# Video.net
KiCad netlist of a schematic drawn in Altium Designer
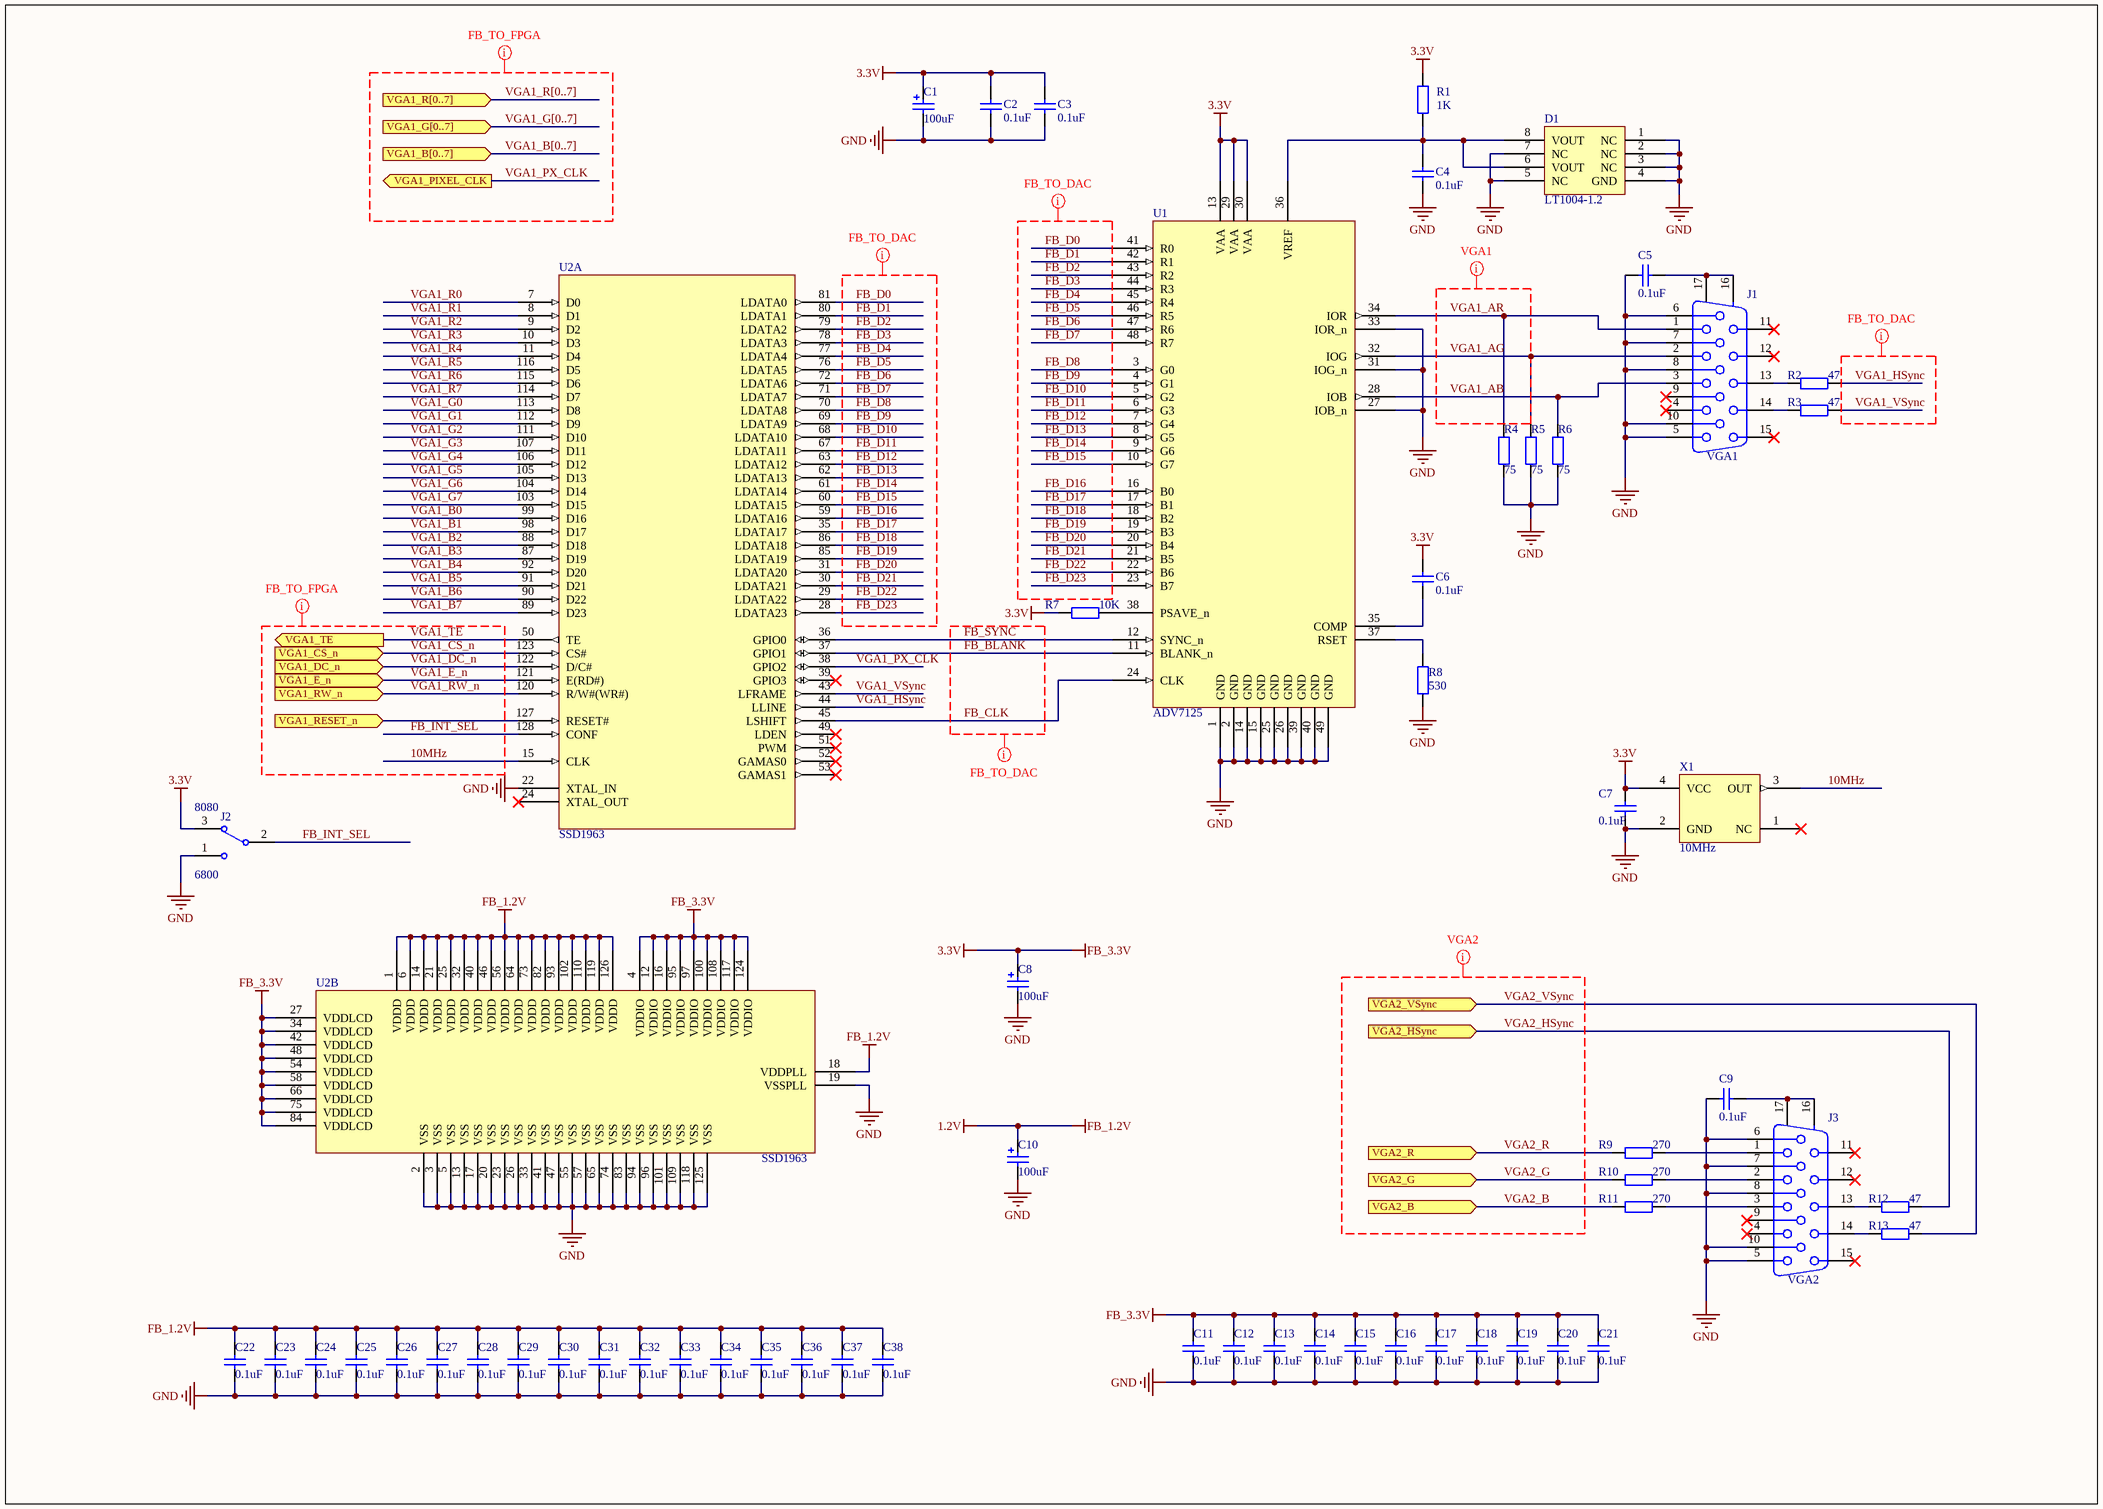
[diagram p0: Video.SchDoc]

(export (version "E")
  (design (tool "Eeschema 10.0.6"))
  (components
    (comp (ref "C1")
      (value "100uF")
      (footprint "C1206_POLARIZED")
      (description "Polarized Capacitor (Axial)")
      (fields (field (name "Comment") "Cap Pol2") (field (name "PUBLISHER") "Altium Limited"))
      (libsource (lib "Miscellaneous Devices") (part "Cap Pol2"))
    )
    (comp (ref "C2")
      (value "0.1uF")
      (footprint "0402")
      (description "Capacitor")
      (fields (field (name "Comment") "Cap") (field (name "PUBLISHER") "Altium Limited"))
      (libsource (lib "Miscellaneous Devices") (part "Cap"))
    )
    (comp (ref "C3")
      (value "0.1uF")
      (footprint "0402")
      (description "Capacitor")
      (fields (field (name "Comment") "Cap") (field (name "PUBLISHER") "Altium Limited"))
      (libsource (lib "Miscellaneous Devices") (part "Cap"))
    )
    (comp (ref "C4")
      (value "0.1uF")
      (footprint "0402")
      (description "Capacitor")
      (fields (field (name "Comment") "Cap") (field (name "PUBLISHER") "Altium Limited"))
      (libsource (lib "Miscellaneous Devices") (part "Cap"))
    )
    (comp (ref "C5")
      (value "0.1uF")
      (footprint "0402")
      (description "Capacitor")
      (fields (field (name "Comment") "Cap") (field (name "PUBLISHER") "Altium Limited"))
      (libsource (lib "Miscellaneous Devices") (part "Cap"))
    )
    (comp (ref "C6")
      (value "0.1uF")
      (footprint "0402")
      (description "Capacitor")
      (fields (field (name "Comment") "Cap") (field (name "PUBLISHER") "Altium Limited"))
      (libsource (lib "Miscellaneous Devices") (part "Cap"))
    )
    (comp (ref "C7")
      (value "0.1uF")
      (footprint "0402")
      (description "Capacitor")
      (fields (field (name "Comment") "Cap") (field (name "PUBLISHER") "Altium Limited"))
      (libsource (lib "Miscellaneous Devices") (part "Cap"))
    )
    (comp (ref "C8")
      (value "100uF")
      (footprint "C1206_POLARIZED")
      (description "Polarized Capacitor (Axial)")
      (fields (field (name "Comment") "Cap Pol2") (field (name "PUBLISHER") "Altium Limited"))
      (libsource (lib "Miscellaneous Devices") (part "Cap Pol2"))
    )
    (comp (ref "C9")
      (value "0.1uF")
      (footprint "0402")
      (description "Capacitor")
      (fields (field (name "Comment") "Cap") (field (name "PUBLISHER") "Altium Limited"))
      (libsource (lib "Miscellaneous Devices") (part "Cap"))
    )
    (comp (ref "C10")
      (value "100uF")
      (footprint "C1206_POLARIZED")
      (description "Polarized Capacitor (Axial)")
      (fields (field (name "Comment") "Cap Pol2") (field (name "PUBLISHER") "Altium Limited"))
      (libsource (lib "Miscellaneous Devices") (part "Cap Pol2"))
    )
    (comp (ref "C11")
      (value "0.1uF")
      (footprint "0402")
      (description "Capacitor")
      (fields (field (name "Comment") "Cap") (field (name "PUBLISHER") "Altium Limited"))
      (libsource (lib "Miscellaneous Devices") (part "Cap"))
    )
    (comp (ref "C12")
      (value "0.1uF")
      (footprint "0402")
      (description "Capacitor")
      (fields (field (name "Comment") "Cap") (field (name "PUBLISHER") "Altium Limited"))
      (libsource (lib "Miscellaneous Devices") (part "Cap"))
    )
    (comp (ref "C13")
      (value "0.1uF")
      (footprint "0402")
      (description "Capacitor")
      (fields (field (name "Comment") "Cap") (field (name "PUBLISHER") "Altium Limited"))
      (libsource (lib "Miscellaneous Devices") (part "Cap"))
    )
    (comp (ref "C14")
      (value "0.1uF")
      (footprint "0402")
      (description "Capacitor")
      (fields (field (name "Comment") "Cap") (field (name "PUBLISHER") "Altium Limited"))
      (libsource (lib "Miscellaneous Devices") (part "Cap"))
    )
    (comp (ref "C15")
      (value "0.1uF")
      (footprint "0402")
      (description "Capacitor")
      (fields (field (name "Comment") "Cap") (field (name "PUBLISHER") "Altium Limited"))
      (libsource (lib "Miscellaneous Devices") (part "Cap"))
    )
    (comp (ref "C16")
      (value "0.1uF")
      (footprint "0402")
      (description "Capacitor")
      (fields (field (name "Comment") "Cap") (field (name "PUBLISHER") "Altium Limited"))
      (libsource (lib "Miscellaneous Devices") (part "Cap"))
    )
    (comp (ref "C17")
      (value "0.1uF")
      (footprint "0402")
      (description "Capacitor")
      (fields (field (name "Comment") "Cap") (field (name "PUBLISHER") "Altium Limited"))
      (libsource (lib "Miscellaneous Devices") (part "Cap"))
    )
    (comp (ref "C18")
      (value "0.1uF")
      (footprint "0402")
      (description "Capacitor")
      (fields (field (name "Comment") "Cap") (field (name "PUBLISHER") "Altium Limited"))
      (libsource (lib "Miscellaneous Devices") (part "Cap"))
    )
    (comp (ref "C19")
      (value "0.1uF")
      (footprint "0402")
      (description "Capacitor")
      (fields (field (name "Comment") "Cap") (field (name "PUBLISHER") "Altium Limited"))
      (libsource (lib "Miscellaneous Devices") (part "Cap"))
    )
    (comp (ref "C20")
      (value "0.1uF")
      (footprint "0402")
      (description "Capacitor")
      (fields (field (name "Comment") "Cap") (field (name "PUBLISHER") "Altium Limited"))
      (libsource (lib "Miscellaneous Devices") (part "Cap"))
    )
    (comp (ref "C21")
      (value "0.1uF")
      (footprint "0402")
      (description "Capacitor")
      (fields (field (name "Comment") "Cap") (field (name "PUBLISHER") "Altium Limited"))
      (libsource (lib "Miscellaneous Devices") (part "Cap"))
    )
    (comp (ref "C22")
      (value "0.1uF")
      (footprint "0402")
      (description "Capacitor")
      (fields (field (name "Comment") "Cap") (field (name "PUBLISHER") "Altium Limited"))
      (libsource (lib "Miscellaneous Devices") (part "Cap"))
    )
    (comp (ref "C23")
      (value "0.1uF")
      (footprint "0402")
      (description "Capacitor")
      (fields (field (name "Comment") "Cap") (field (name "PUBLISHER") "Altium Limited"))
      (libsource (lib "Miscellaneous Devices") (part "Cap"))
    )
    (comp (ref "C24")
      (value "0.1uF")
      (footprint "0402")
      (description "Capacitor")
      (fields (field (name "Comment") "Cap") (field (name "PUBLISHER") "Altium Limited"))
      (libsource (lib "Miscellaneous Devices") (part "Cap"))
    )
    (comp (ref "C25")
      (value "0.1uF")
      (footprint "0402")
      (description "Capacitor")
      (fields (field (name "Comment") "Cap") (field (name "PUBLISHER") "Altium Limited"))
      (libsource (lib "Miscellaneous Devices") (part "Cap"))
    )
    (comp (ref "C26")
      (value "0.1uF")
      (footprint "0402")
      (description "Capacitor")
      (fields (field (name "Comment") "Cap") (field (name "PUBLISHER") "Altium Limited"))
      (libsource (lib "Miscellaneous Devices") (part "Cap"))
    )
    (comp (ref "C27")
      (value "0.1uF")
      (footprint "0402")
      (description "Capacitor")
      (fields (field (name "Comment") "Cap") (field (name "PUBLISHER") "Altium Limited"))
      (libsource (lib "Miscellaneous Devices") (part "Cap"))
    )
    (comp (ref "C28")
      (value "0.1uF")
      (footprint "0402")
      (description "Capacitor")
      (fields (field (name "Comment") "Cap") (field (name "PUBLISHER") "Altium Limited"))
      (libsource (lib "Miscellaneous Devices") (part "Cap"))
    )
    (comp (ref "C29")
      (value "0.1uF")
      (footprint "0402")
      (description "Capacitor")
      (fields (field (name "Comment") "Cap") (field (name "PUBLISHER") "Altium Limited"))
      (libsource (lib "Miscellaneous Devices") (part "Cap"))
    )
    (comp (ref "C30")
      (value "0.1uF")
      (footprint "0402")
      (description "Capacitor")
      (fields (field (name "Comment") "Cap") (field (name "PUBLISHER") "Altium Limited"))
      (libsource (lib "Miscellaneous Devices") (part "Cap"))
    )
    (comp (ref "C31")
      (value "0.1uF")
      (footprint "0402")
      (description "Capacitor")
      (fields (field (name "Comment") "Cap") (field (name "PUBLISHER") "Altium Limited"))
      (libsource (lib "Miscellaneous Devices") (part "Cap"))
    )
    (comp (ref "C32")
      (value "0.1uF")
      (footprint "0402")
      (description "Capacitor")
      (fields (field (name "Comment") "Cap") (field (name "PUBLISHER") "Altium Limited"))
      (libsource (lib "Miscellaneous Devices") (part "Cap"))
    )
    (comp (ref "C33")
      (value "0.1uF")
      (footprint "0402")
      (description "Capacitor")
      (fields (field (name "Comment") "Cap") (field (name "PUBLISHER") "Altium Limited"))
      (libsource (lib "Miscellaneous Devices") (part "Cap"))
    )
    (comp (ref "C34")
      (value "0.1uF")
      (footprint "0402")
      (description "Capacitor")
      (fields (field (name "Comment") "Cap") (field (name "PUBLISHER") "Altium Limited"))
      (libsource (lib "Miscellaneous Devices") (part "Cap"))
    )
    (comp (ref "C35")
      (value "0.1uF")
      (footprint "0402")
      (description "Capacitor")
      (fields (field (name "Comment") "Cap") (field (name "PUBLISHER") "Altium Limited"))
      (libsource (lib "Miscellaneous Devices") (part "Cap"))
    )
    (comp (ref "C36")
      (value "0.1uF")
      (footprint "0402")
      (description "Capacitor")
      (fields (field (name "Comment") "Cap") (field (name "PUBLISHER") "Altium Limited"))
      (libsource (lib "Miscellaneous Devices") (part "Cap"))
    )
    (comp (ref "C37")
      (value "0.1uF")
      (footprint "0402")
      (description "Capacitor")
      (fields (field (name "Comment") "Cap") (field (name "PUBLISHER") "Altium Limited"))
      (libsource (lib "Miscellaneous Devices") (part "Cap"))
    )
    (comp (ref "C38")
      (value "0.1uF")
      (footprint "0402")
      (description "Capacitor")
      (fields (field (name "Comment") "Cap") (field (name "PUBLISHER") "Altium Limited"))
      (libsource (lib "Miscellaneous Devices") (part "Cap"))
    )
    (comp (ref "D1") (value "LT1004-1.2") (footprint "S8") (libsource (lib "FPGA_board") (part "LT1004-1.2")))
    (comp (ref "J1")
      (value "VGA1")
      (footprint "FPGA_board:VGA_Socket")
      (description "Receptacle Assembly, 15-Pin, Sim Line Connector")
      (libsource (lib "Miscellaneous Connectors") (part "Connector 15"))
    )
    (comp (ref "J2")
      (value "FB_INTERFACE")
      (footprint "HDR1X3")
      (fields (field (name "PUBLISHER") "Altium Limited"))
      (libsource (lib "Miscellaneous Devices") (part "SW-SPDT"))
    )
    (comp (ref "J3")
      (value "VGA2")
      (footprint "FPGA_board:VGA_Socket")
      (description "Receptacle Assembly, 15-Pin, Sim Line Connector")
      (libsource (lib "Miscellaneous Connectors") (part "Connector 15"))
    )
    (comp (ref "R1")
      (value "1K")
      (footprint "J1-0603")
      (description "Resistor")
      (fields (field (name "Comment") "Res2") (field (name "PUBLISHER") "Altium Limited"))
      (libsource (lib "") (part "Res2_3"))
    )
    (comp (ref "R2")
      (value "47")
      (footprint "J1-0603")
      (description "Resistor")
      (fields (field (name "Comment") "Res2") (field (name "PUBLISHER") "Altium Limited"))
      (libsource (lib "Miscellaneous Devices") (part "Res2"))
    )
    (comp (ref "R3")
      (value "47")
      (footprint "J1-0603")
      (description "Resistor")
      (fields (field (name "Comment") "Res2") (field (name "PUBLISHER") "Altium Limited"))
      (libsource (lib "Miscellaneous Devices") (part "Res2"))
    )
    (comp (ref "R4")
      (value "75")
      (footprint "J1-0603")
      (description "Resistor")
      (fields (field (name "Comment") "Res2") (field (name "PUBLISHER") "Altium Limited"))
      (libsource (lib "") (part "Res2_3"))
    )
    (comp (ref "R5")
      (value "75")
      (footprint "J1-0603")
      (description "Resistor")
      (fields (field (name "Comment") "Res2") (field (name "PUBLISHER") "Altium Limited"))
      (libsource (lib "") (part "Res2_1"))
    )
    (comp (ref "R6")
      (value "75")
      (footprint "J1-0603")
      (description "Resistor")
      (fields (field (name "Comment") "Res2") (field (name "PUBLISHER") "Altium Limited"))
      (libsource (lib "") (part "Res2_1"))
    )
    (comp (ref "R7")
      (value "10K")
      (footprint "J1-0603")
      (description "Resistor")
      (fields (field (name "Comment") "Res2") (field (name "PUBLISHER") "Altium Limited"))
      (libsource (lib "Miscellaneous Devices") (part "Res2"))
    )
    (comp (ref "R8")
      (value "530")
      (footprint "J1-0603")
      (description "Resistor")
      (fields (field (name "Comment") "Res2") (field (name "PUBLISHER") "Altium Limited"))
      (libsource (lib "") (part "Res2_3"))
    )
    (comp (ref "R9")
      (value "270")
      (footprint "6-0805_N")
      (description "Resistor")
      (fields (field (name "Comment") "Res2") (field (name "PUBLISHER") "Altium Limited"))
      (libsource (lib "") (part "Res2_2"))
    )
    (comp (ref "R10")
      (value "270")
      (footprint "6-0805_N")
      (description "Resistor")
      (fields (field (name "Comment") "Res2") (field (name "PUBLISHER") "Altium Limited"))
      (libsource (lib "") (part "Res2_2"))
    )
    (comp (ref "R11")
      (value "270")
      (footprint "6-0805_N")
      (description "Resistor")
      (fields (field (name "Comment") "Res2") (field (name "PUBLISHER") "Altium Limited"))
      (libsource (lib "") (part "Res2_2"))
    )
    (comp (ref "R12")
      (value "47")
      (footprint "J1-0603")
      (description "Resistor")
      (fields (field (name "Comment") "Res2") (field (name "PUBLISHER") "Altium Limited"))
      (libsource (lib "Miscellaneous Devices") (part "Res2"))
    )
    (comp (ref "R13")
      (value "47")
      (footprint "J1-0603")
      (description "Resistor")
      (fields (field (name "Comment") "Res2") (field (name "PUBLISHER") "Altium Limited"))
      (libsource (lib "Miscellaneous Devices") (part "Res2"))
    )
    (comp (ref "U1")
      (value "ADV7125")
      (footprint "LFCSP_VQ48")
      (libsource (lib "FPGA_board") (part "ADV7125"))
    )
    (comp (ref "U2")
      (value "SSD1963")
      (footprint "LQFP128-0.4")
      (libsource (lib "FPGA_board") (part "SSD1963"))
    )
    (comp (ref "X1")
      (value "10MHz")
      (footprint "FOX924")
      (libsource (lib "FPGA_board") (part "FOX924B-10MHz"))
    )
  )
  (nets
    (net (code "1") (name "/10MHz") (class "Default")
      (node (ref "U2") (pin "15") (pinfunction "CLK_15") (pintype "input"))
      (node (ref "X1") (pin "3") (pinfunction "OUT_3") (pintype "output"))
    )
    (net (code "2") (name "/FB_BLANK") (class "Default")
      (node (ref "U1") (pin "11") (pinfunction "BLANK_n_11") (pintype "input"))
      (node (ref "U2") (pin "37") (pinfunction "GPIO1_37") (pintype "bidirectional"))
    )
    (net (code "3") (name "/FB_CLK") (class "Default")
      (node (ref "U1") (pin "24") (pinfunction "CLK_24") (pintype "input"))
      (node (ref "U2") (pin "45") (pinfunction "LSHIFT_45") (pintype "output"))
    )
    (net (code "4") (name "/FB_D0") (class "Default")
      (node (ref "U1") (pin "41") (pinfunction "R0_41") (pintype "input"))
      (node (ref "U2") (pin "81") (pinfunction "LDATA0_81") (pintype "output"))
    )
    (net (code "5") (name "/FB_D1") (class "Default")
      (node (ref "U1") (pin "42") (pinfunction "R1_42") (pintype "input"))
      (node (ref "U2") (pin "80") (pinfunction "LDATA1_80") (pintype "output"))
    )
    (net (code "6") (name "/FB_D2") (class "Default")
      (node (ref "U1") (pin "43") (pinfunction "R2_43") (pintype "input"))
      (node (ref "U2") (pin "79") (pinfunction "LDATA2_79") (pintype "output"))
    )
    (net (code "7") (name "/FB_D3") (class "Default")
      (node (ref "U1") (pin "44") (pinfunction "R3_44") (pintype "input"))
      (node (ref "U2") (pin "78") (pinfunction "LDATA3_78") (pintype "output"))
    )
    (net (code "8") (name "/FB_D4") (class "Default")
      (node (ref "U1") (pin "45") (pinfunction "R4_45") (pintype "input"))
      (node (ref "U2") (pin "77") (pinfunction "LDATA4_77") (pintype "output"))
    )
    (net (code "9") (name "/FB_D5") (class "Default")
      (node (ref "U1") (pin "46") (pinfunction "R5_46") (pintype "input"))
      (node (ref "U2") (pin "76") (pinfunction "LDATA5_76") (pintype "output"))
    )
    (net (code "10") (name "/FB_D6") (class "Default")
      (node (ref "U1") (pin "47") (pinfunction "R6_47") (pintype "input"))
      (node (ref "U2") (pin "72") (pinfunction "LDATA6_72") (pintype "output"))
    )
    (net (code "11") (name "/FB_D7") (class "Default")
      (node (ref "U1") (pin "48") (pinfunction "R7_48") (pintype "input"))
      (node (ref "U2") (pin "71") (pinfunction "LDATA7_71") (pintype "output"))
    )
    (net (code "12") (name "/FB_D8") (class "Default")
      (node (ref "U1") (pin "3") (pinfunction "G0_3") (pintype "input"))
      (node (ref "U2") (pin "70") (pinfunction "LDATA8_70") (pintype "output"))
    )
    (net (code "13") (name "/FB_D9") (class "Default")
      (node (ref "U1") (pin "4") (pinfunction "G1_4") (pintype "input"))
      (node (ref "U2") (pin "69") (pinfunction "LDATA9_69") (pintype "output"))
    )
    (net (code "14") (name "/FB_D10") (class "Default")
      (node (ref "U1") (pin "5") (pinfunction "G2_5") (pintype "input"))
      (node (ref "U2") (pin "68") (pinfunction "LDATA10_68") (pintype "output"))
    )
    (net (code "15") (name "/FB_D11") (class "Default")
      (node (ref "U1") (pin "6") (pinfunction "G3_6") (pintype "input"))
      (node (ref "U2") (pin "67") (pinfunction "LDATA11_67") (pintype "output"))
    )
    (net (code "16") (name "/FB_D12") (class "Default")
      (node (ref "U1") (pin "7") (pinfunction "G4_7") (pintype "input"))
      (node (ref "U2") (pin "63") (pinfunction "LDATA12_63") (pintype "output"))
    )
    (net (code "17") (name "/FB_D13") (class "Default")
      (node (ref "U1") (pin "8") (pinfunction "G5_8") (pintype "input"))
      (node (ref "U2") (pin "62") (pinfunction "LDATA13_62") (pintype "output"))
    )
    (net (code "18") (name "/FB_D14") (class "Default")
      (node (ref "U1") (pin "9") (pinfunction "G6_9") (pintype "input"))
      (node (ref "U2") (pin "61") (pinfunction "LDATA14_61") (pintype "output"))
    )
    (net (code "19") (name "/FB_D15") (class "Default")
      (node (ref "U1") (pin "10") (pinfunction "G7_10") (pintype "input"))
      (node (ref "U2") (pin "60") (pinfunction "LDATA15_60") (pintype "output"))
    )
    (net (code "20") (name "/FB_D16") (class "Default")
      (node (ref "U1") (pin "16") (pinfunction "B0_16") (pintype "input"))
      (node (ref "U2") (pin "59") (pinfunction "LDATA16_59") (pintype "output"))
    )
    (net (code "21") (name "/FB_D17") (class "Default")
      (node (ref "U1") (pin "17") (pinfunction "B1_17") (pintype "input"))
      (node (ref "U2") (pin "35") (pinfunction "LDATA17_35") (pintype "output"))
    )
    (net (code "22") (name "/FB_D18") (class "Default")
      (node (ref "U1") (pin "18") (pinfunction "B2_18") (pintype "input"))
      (node (ref "U2") (pin "86") (pinfunction "LDATA18_86") (pintype "output"))
    )
    (net (code "23") (name "/FB_D19") (class "Default")
      (node (ref "U1") (pin "19") (pinfunction "B3_19") (pintype "input"))
      (node (ref "U2") (pin "85") (pinfunction "LDATA19_85") (pintype "output"))
    )
    (net (code "24") (name "/FB_D20") (class "Default")
      (node (ref "U1") (pin "20") (pinfunction "B4_20") (pintype "input"))
      (node (ref "U2") (pin "31") (pinfunction "LDATA20_31") (pintype "output"))
    )
    (net (code "25") (name "/FB_D21") (class "Default")
      (node (ref "U1") (pin "21") (pinfunction "B5_21") (pintype "input"))
      (node (ref "U2") (pin "30") (pinfunction "LDATA21_30") (pintype "output"))
    )
    (net (code "26") (name "/FB_D22") (class "Default")
      (node (ref "U1") (pin "22") (pinfunction "B6_22") (pintype "input"))
      (node (ref "U2") (pin "29") (pinfunction "LDATA22_29") (pintype "output"))
    )
    (net (code "27") (name "/FB_D23") (class "Default")
      (node (ref "U1") (pin "23") (pinfunction "B7_23") (pintype "input"))
      (node (ref "U2") (pin "28") (pinfunction "LDATA23_28") (pintype "output"))
    )
    (net (code "28") (name "/FB_INT_SEL") (class "Default")
      (node (ref "J2") (pin "2") (pinfunction "2_2") (pintype "passive"))
      (node (ref "U2") (pin "128") (pinfunction "CONF_128") (pintype "input"))
    )
    (net (code "29") (name "/FB_SYNC") (class "Default")
      (node (ref "U1") (pin "12") (pinfunction "SYNC_n_12") (pintype "input"))
      (node (ref "U2") (pin "36") (pinfunction "GPIO0_36") (pintype "bidirectional"))
    )
    (net (code "30") (name "/VGA1_AB") (class "Default")
      (node (ref "J1") (pin "3") (pinfunction "3_3") (pintype "passive"))
      (node (ref "R6") (pin "1") (pinfunction "1_1") (pintype "passive"))
      (node (ref "U1") (pin "28") (pinfunction "IOB_28") (pintype "output"))
    )
    (net (code "31") (name "/VGA1_AG") (class "Default")
      (node (ref "J1") (pin "2") (pinfunction "2_2") (pintype "passive"))
      (node (ref "R5") (pin "1") (pinfunction "1_1") (pintype "passive"))
      (node (ref "U1") (pin "32") (pinfunction "IOG_32") (pintype "output"))
    )
    (net (code "32") (name "/VGA1_AR") (class "Default")
      (node (ref "J1") (pin "1") (pinfunction "1_1") (pintype "passive"))
      (node (ref "R4") (pin "2") (pinfunction "2_2") (pintype "passive"))
      (node (ref "U1") (pin "34") (pinfunction "IOR_34") (pintype "output"))
    )
    (net (code "33") (name "/VGA1_B0") (class "Default")
      (node (ref "U2") (pin "99") (pinfunction "D16_99") (pintype "input"))
    )
    (net (code "34") (name "/VGA1_B1") (class "Default")
      (node (ref "U2") (pin "98") (pinfunction "D17_98") (pintype "input"))
    )
    (net (code "35") (name "/VGA1_B2") (class "Default")
      (node (ref "U2") (pin "88") (pinfunction "D18_88") (pintype "input"))
    )
    (net (code "36") (name "/VGA1_B3") (class "Default")
      (node (ref "U2") (pin "87") (pinfunction "D19_87") (pintype "input"))
    )
    (net (code "37") (name "/VGA1_B4") (class "Default")
      (node (ref "U2") (pin "92") (pinfunction "D20_92") (pintype "input"))
    )
    (net (code "38") (name "/VGA1_B5") (class "Default")
      (node (ref "U2") (pin "91") (pinfunction "D21_91") (pintype "input"))
    )
    (net (code "39") (name "/VGA1_B6") (class "Default")
      (node (ref "U2") (pin "90") (pinfunction "D22_90") (pintype "input"))
    )
    (net (code "40") (name "/VGA1_B7") (class "Default")
      (node (ref "U2") (pin "89") (pinfunction "D23_89") (pintype "input"))
    )
    (net (code "42") (name "/VGA1_CS_n") (class "Default")
      (node (ref "U2") (pin "123") (pinfunction "CS#_123") (pintype "input"))
    )
    (net (code "43") (name "/VGA1_DC_n") (class "Default")
      (node (ref "U2") (pin "122") (pinfunction "D/C#_122") (pintype "input"))
    )
    (net (code "44") (name "/VGA1_E_n") (class "Default")
      (node (ref "U2") (pin "121") (pinfunction "E(RD#)_121") (pintype "input"))
    )
    (net (code "45") (name "/VGA1_G0") (class "Default")
      (node (ref "U2") (pin "113") (pinfunction "D8_113") (pintype "input"))
    )
    (net (code "46") (name "/VGA1_G1") (class "Default")
      (node (ref "U2") (pin "112") (pinfunction "D9_112") (pintype "input"))
    )
    (net (code "47") (name "/VGA1_G2") (class "Default")
      (node (ref "U2") (pin "111") (pinfunction "D10_111") (pintype "input"))
    )
    (net (code "48") (name "/VGA1_G3") (class "Default")
      (node (ref "U2") (pin "107") (pinfunction "D11_107") (pintype "input"))
    )
    (net (code "49") (name "/VGA1_G4") (class "Default")
      (node (ref "U2") (pin "106") (pinfunction "D12_106") (pintype "input"))
    )
    (net (code "50") (name "/VGA1_G5") (class "Default")
      (node (ref "U2") (pin "105") (pinfunction "D13_105") (pintype "input"))
    )
    (net (code "51") (name "/VGA1_G6") (class "Default")
      (node (ref "U2") (pin "104") (pinfunction "D14_104") (pintype "input"))
    )
    (net (code "52") (name "/VGA1_G7") (class "Default")
      (node (ref "U2") (pin "103") (pinfunction "D15_103") (pintype "input"))
    )
    (net (code "54") (name "/VGA1_HSync") (class "Default")
      (node (ref "R2") (pin "2") (pinfunction "2_2") (pintype "passive"))
      (node (ref "U2") (pin "44") (pinfunction "LLINE_44") (pintype "output"))
    )
    (net (code "55") (name "/VGA1_PX_CLK") (class "Default")
      (node (ref "U2") (pin "38") (pinfunction "GPIO2_38") (pintype "bidirectional"))
    )
    (net (code "56") (name "/VGA1_R0") (class "Default")
      (node (ref "U2") (pin "7") (pinfunction "D0_7") (pintype "input"))
    )
    (net (code "57") (name "/VGA1_R1") (class "Default")
      (node (ref "U2") (pin "8") (pinfunction "D1_8") (pintype "input"))
    )
    (net (code "58") (name "/VGA1_R2") (class "Default")
      (node (ref "U2") (pin "9") (pinfunction "D2_9") (pintype "input"))
    )
    (net (code "59") (name "/VGA1_R3") (class "Default")
      (node (ref "U2") (pin "10") (pinfunction "D3_10") (pintype "input"))
    )
    (net (code "60") (name "/VGA1_R4") (class "Default")
      (node (ref "U2") (pin "11") (pinfunction "D4_11") (pintype "input"))
    )
    (net (code "61") (name "/VGA1_R5") (class "Default")
      (node (ref "U2") (pin "116") (pinfunction "D5_116") (pintype "input"))
    )
    (net (code "62") (name "/VGA1_R6") (class "Default")
      (node (ref "U2") (pin "115") (pinfunction "D6_115") (pintype "input"))
    )
    (net (code "63") (name "/VGA1_R7") (class "Default")
      (node (ref "U2") (pin "114") (pinfunction "D7_114") (pintype "input"))
    )
    (net (code "64") (name "/VGA1_RESET_n") (class "Default")
      (node (ref "U2") (pin "127") (pinfunction "RESET#_127") (pintype "input"))
    )
    (net (code "65") (name "/VGA1_RW_n") (class "Default")
      (node (ref "U2") (pin "120") (pinfunction "R/W#(WR#)_120") (pintype "input"))
    )
    (net (code "67") (name "/VGA1_TE") (class "Default")
      (node (ref "U2") (pin "50") (pinfunction "TE_50") (pintype "output"))
    )
    (net (code "68") (name "/VGA1_VSync") (class "Default")
      (node (ref "R3") (pin "2") (pinfunction "2_2") (pintype "passive"))
      (node (ref "U2") (pin "43") (pinfunction "LFRAME_43") (pintype "output"))
    )
    (net (code "69") (name "/VGA2_B") (class "Default")
      (node (ref "R11") (pin "2") (pinfunction "2_2") (pintype "passive"))
    )
    (net (code "70") (name "/VGA2_G") (class "Default")
      (node (ref "R10") (pin "2") (pinfunction "2_2") (pintype "passive"))
    )
    (net (code "71") (name "/VGA2_HSync") (class "Default")
      (node (ref "R12") (pin "2") (pinfunction "2_2") (pintype "passive"))
    )
    (net (code "72") (name "/VGA2_R") (class "Default")
      (node (ref "R9") (pin "2") (pinfunction "2_2") (pintype "passive"))
    )
    (net (code "73") (name "/VGA2_VSync") (class "Default")
      (node (ref "R13") (pin "2") (pinfunction "2_2") (pintype "passive"))
    )
    (net (code "74") (name "1.2V") (class "Default")
      (node (ref "C10") (pin "1") (pinfunction "1_1") (pintype "passive"))
      (node (ref "C22") (pin "1") (pinfunction "1_1") (pintype "passive"))
      (node (ref "C23") (pin "1") (pinfunction "1_1") (pintype "passive"))
      (node (ref "C24") (pin "1") (pinfunction "1_1") (pintype "passive"))
      (node (ref "C25") (pin "1") (pinfunction "1_1") (pintype "passive"))
      (node (ref "C26") (pin "1") (pinfunction "1_1") (pintype "passive"))
      (node (ref "C27") (pin "1") (pinfunction "1_1") (pintype "passive"))
      (node (ref "C28") (pin "1") (pinfunction "1_1") (pintype "passive"))
      (node (ref "C29") (pin "1") (pinfunction "1_1") (pintype "passive"))
      (node (ref "C30") (pin "1") (pinfunction "1_1") (pintype "passive"))
      (node (ref "C31") (pin "1") (pinfunction "1_1") (pintype "passive"))
      (node (ref "C32") (pin "1") (pinfunction "1_1") (pintype "passive"))
      (node (ref "C33") (pin "1") (pinfunction "1_1") (pintype "passive"))
      (node (ref "C34") (pin "1") (pinfunction "1_1") (pintype "passive"))
      (node (ref "C35") (pin "1") (pinfunction "1_1") (pintype "passive"))
      (node (ref "C36") (pin "1") (pinfunction "1_1") (pintype "passive"))
      (node (ref "C37") (pin "1") (pinfunction "1_1") (pintype "passive"))
      (node (ref "C38") (pin "1") (pinfunction "1_1") (pintype "passive"))
      (node (ref "U2") (pin "1") (pinfunction "VDDD_1") (pintype "power_in"))
      (node (ref "U2") (pin "102") (pinfunction "VDDD_102") (pintype "power_in"))
      (node (ref "U2") (pin "110") (pinfunction "VDDD_110") (pintype "power_in"))
      (node (ref "U2") (pin "119") (pinfunction "VDDD_119") (pintype "power_in"))
      (node (ref "U2") (pin "126") (pinfunction "VDDD_126") (pintype "power_in"))
      (node (ref "U2") (pin "14") (pinfunction "VDDD_14") (pintype "power_in"))
      (node (ref "U2") (pin "18") (pinfunction "VDDPLL_18") (pintype "power_in"))
      (node (ref "U2") (pin "21") (pinfunction "VDDD_21") (pintype "power_in"))
      (node (ref "U2") (pin "25") (pinfunction "VDDD_25") (pintype "power_in"))
      (node (ref "U2") (pin "32") (pinfunction "VDDD_32") (pintype "power_in"))
      (node (ref "U2") (pin "40") (pinfunction "VDDD_40") (pintype "power_in"))
      (node (ref "U2") (pin "46") (pinfunction "VDDD_46") (pintype "power_in"))
      (node (ref "U2") (pin "56") (pinfunction "VDDD_56") (pintype "power_in"))
      (node (ref "U2") (pin "6") (pinfunction "VDDD_6") (pintype "power_in"))
      (node (ref "U2") (pin "64") (pinfunction "VDDD_64") (pintype "power_in"))
      (node (ref "U2") (pin "73") (pinfunction "VDDD_73") (pintype "power_in"))
      (node (ref "U2") (pin "82") (pinfunction "VDDD_82") (pintype "power_in"))
      (node (ref "U2") (pin "93") (pinfunction "VDDD_93") (pintype "power_in"))
    )
    (net (code "75") (name "3.3V") (class "Default")
      (node (ref "C1") (pin "1") (pinfunction "1_1") (pintype "passive"))
      (node (ref "C11") (pin "1") (pinfunction "1_1") (pintype "passive"))
      (node (ref "C12") (pin "1") (pinfunction "1_1") (pintype "passive"))
      (node (ref "C13") (pin "1") (pinfunction "1_1") (pintype "passive"))
      (node (ref "C14") (pin "1") (pinfunction "1_1") (pintype "passive"))
      (node (ref "C15") (pin "1") (pinfunction "1_1") (pintype "passive"))
      (node (ref "C16") (pin "1") (pinfunction "1_1") (pintype "passive"))
      (node (ref "C17") (pin "1") (pinfunction "1_1") (pintype "passive"))
      (node (ref "C18") (pin "1") (pinfunction "1_1") (pintype "passive"))
      (node (ref "C19") (pin "1") (pinfunction "1_1") (pintype "passive"))
      (node (ref "C2") (pin "2") (pinfunction "2_2") (pintype "passive"))
      (node (ref "C20") (pin "1") (pinfunction "1_1") (pintype "passive"))
      (node (ref "C21") (pin "1") (pinfunction "1_1") (pintype "passive"))
      (node (ref "C3") (pin "2") (pinfunction "2_2") (pintype "passive"))
      (node (ref "C6") (pin "2") (pinfunction "2_2") (pintype "passive"))
      (node (ref "C7") (pin "1") (pinfunction "1_1") (pintype "passive"))
      (node (ref "C8") (pin "1") (pinfunction "1_1") (pintype "passive"))
      (node (ref "J2") (pin "3") (pinfunction "3_3") (pintype "passive"))
      (node (ref "R1") (pin "2") (pinfunction "2_2") (pintype "passive"))
      (node (ref "R7") (pin "1") (pinfunction "1_1") (pintype "passive"))
      (node (ref "U1") (pin "13") (pinfunction "VAA_13") (pintype "power_in"))
      (node (ref "U1") (pin "29") (pinfunction "VAA_29") (pintype "power_in"))
      (node (ref "U1") (pin "30") (pinfunction "VAA_30") (pintype "power_in"))
      (node (ref "U2") (pin "100") (pinfunction "VDDIO_100") (pintype "power_in"))
      (node (ref "U2") (pin "108") (pinfunction "VDDIO_108") (pintype "power_in"))
      (node (ref "U2") (pin "117") (pinfunction "VDDIO_117") (pintype "power_in"))
      (node (ref "U2") (pin "12") (pinfunction "VDDIO_12") (pintype "power_in"))
      (node (ref "U2") (pin "124") (pinfunction "VDDIO_124") (pintype "power_in"))
      (node (ref "U2") (pin "16") (pinfunction "VDDIO_16") (pintype "power_in"))
      (node (ref "U2") (pin "27") (pinfunction "VDDLCD_27") (pintype "power_in"))
      (node (ref "U2") (pin "34") (pinfunction "VDDLCD_34") (pintype "power_in"))
      (node (ref "U2") (pin "4") (pinfunction "VDDIO_4") (pintype "power_in"))
      (node (ref "U2") (pin "42") (pinfunction "VDDLCD_42") (pintype "power_in"))
      (node (ref "U2") (pin "48") (pinfunction "VDDLCD_48") (pintype "power_in"))
      (node (ref "U2") (pin "54") (pinfunction "VDDLCD_54") (pintype "power_in"))
      (node (ref "U2") (pin "58") (pinfunction "VDDLCD_58") (pintype "power_in"))
      (node (ref "U2") (pin "66") (pinfunction "VDDLCD_66") (pintype "power_in"))
      (node (ref "U2") (pin "75") (pinfunction "VDDLCD_75") (pintype "power_in"))
      (node (ref "U2") (pin "84") (pinfunction "VDDLCD_84") (pintype "power_in"))
      (node (ref "U2") (pin "95") (pinfunction "VDDIO_95") (pintype "power_in"))
      (node (ref "U2") (pin "97") (pinfunction "VDDIO_97") (pintype "power_in"))
      (node (ref "X1") (pin "4") (pinfunction "VCC_4") (pintype "power_in"))
    )
    (net (code "76") (name "GND") (class "Default")
      (node (ref "C1") (pin "2") (pinfunction "2_2") (pintype "passive"))
      (node (ref "C10") (pin "2") (pinfunction "2_2") (pintype "passive"))
      (node (ref "C11") (pin "2") (pinfunction "2_2") (pintype "passive"))
      (node (ref "C12") (pin "2") (pinfunction "2_2") (pintype "passive"))
      (node (ref "C13") (pin "2") (pinfunction "2_2") (pintype "passive"))
      (node (ref "C14") (pin "2") (pinfunction "2_2") (pintype "passive"))
      (node (ref "C15") (pin "2") (pinfunction "2_2") (pintype "passive"))
      (node (ref "C16") (pin "2") (pinfunction "2_2") (pintype "passive"))
      (node (ref "C17") (pin "2") (pinfunction "2_2") (pintype "passive"))
      (node (ref "C18") (pin "2") (pinfunction "2_2") (pintype "passive"))
      (node (ref "C19") (pin "2") (pinfunction "2_2") (pintype "passive"))
      (node (ref "C2") (pin "1") (pinfunction "1_1") (pintype "passive"))
      (node (ref "C20") (pin "2") (pinfunction "2_2") (pintype "passive"))
      (node (ref "C21") (pin "2") (pinfunction "2_2") (pintype "passive"))
      (node (ref "C22") (pin "2") (pinfunction "2_2") (pintype "passive"))
      (node (ref "C23") (pin "2") (pinfunction "2_2") (pintype "passive"))
      (node (ref "C24") (pin "2") (pinfunction "2_2") (pintype "passive"))
      (node (ref "C25") (pin "2") (pinfunction "2_2") (pintype "passive"))
      (node (ref "C26") (pin "2") (pinfunction "2_2") (pintype "passive"))
      (node (ref "C27") (pin "2") (pinfunction "2_2") (pintype "passive"))
      (node (ref "C28") (pin "2") (pinfunction "2_2") (pintype "passive"))
      (node (ref "C29") (pin "2") (pinfunction "2_2") (pintype "passive"))
      (node (ref "C3") (pin "1") (pinfunction "1_1") (pintype "passive"))
      (node (ref "C30") (pin "2") (pinfunction "2_2") (pintype "passive"))
      (node (ref "C31") (pin "2") (pinfunction "2_2") (pintype "passive"))
      (node (ref "C32") (pin "2") (pinfunction "2_2") (pintype "passive"))
      (node (ref "C33") (pin "2") (pinfunction "2_2") (pintype "passive"))
      (node (ref "C34") (pin "2") (pinfunction "2_2") (pintype "passive"))
      (node (ref "C35") (pin "2") (pinfunction "2_2") (pintype "passive"))
      (node (ref "C36") (pin "2") (pinfunction "2_2") (pintype "passive"))
      (node (ref "C37") (pin "2") (pinfunction "2_2") (pintype "passive"))
      (node (ref "C38") (pin "2") (pinfunction "2_2") (pintype "passive"))
      (node (ref "C4") (pin "2") (pinfunction "2_2") (pintype "passive"))
      (node (ref "C5") (pin "1") (pinfunction "1_1") (pintype "passive"))
      (node (ref "C7") (pin "2") (pinfunction "2_2") (pintype "passive"))
      (node (ref "C8") (pin "2") (pinfunction "2_2") (pintype "passive"))
      (node (ref "C9") (pin "1") (pinfunction "1_1") (pintype "passive"))
      (node (ref "D1") (pin "1") (pinfunction "NC_1") (pintype "passive"))
      (node (ref "D1") (pin "2") (pinfunction "NC_2") (pintype "passive"))
      (node (ref "D1") (pin "3") (pinfunction "NC_3") (pintype "passive"))
      (node (ref "D1") (pin "4") (pinfunction "GND_4") (pintype "passive"))
      (node (ref "D1") (pin "5") (pinfunction "NC_5") (pintype "passive"))
      (node (ref "D1") (pin "7") (pinfunction "NC_7") (pintype "passive"))
      (node (ref "J1") (pin "10") (pinfunction "10_10") (pintype "passive"))
      (node (ref "J1") (pin "5") (pinfunction "5_5") (pintype "passive"))
      (node (ref "J1") (pin "6") (pinfunction "6_6") (pintype "passive"))
      (node (ref "J1") (pin "7") (pinfunction "7_7") (pintype "passive"))
      (node (ref "J1") (pin "8") (pinfunction "8_8") (pintype "passive"))
      (node (ref "J2") (pin "1") (pinfunction "1_1") (pintype "passive"))
      (node (ref "J3") (pin "10") (pinfunction "10_10") (pintype "passive"))
      (node (ref "J3") (pin "5") (pinfunction "5_5") (pintype "passive"))
      (node (ref "J3") (pin "6") (pinfunction "6_6") (pintype "passive"))
      (node (ref "J3") (pin "7") (pinfunction "7_7") (pintype "passive"))
      (node (ref "J3") (pin "8") (pinfunction "8_8") (pintype "passive"))
      (node (ref "R4") (pin "1") (pinfunction "1_1") (pintype "passive"))
      (node (ref "R5") (pin "2") (pinfunction "2_2") (pintype "passive"))
      (node (ref "R6") (pin "2") (pinfunction "2_2") (pintype "passive"))
      (node (ref "R8") (pin "1") (pinfunction "1_1") (pintype "passive"))
      (node (ref "U1") (pin "1") (pinfunction "GND_1") (pintype "power_in"))
      (node (ref "U1") (pin "14") (pinfunction "GND_14") (pintype "power_in"))
      (node (ref "U1") (pin "15") (pinfunction "GND_15") (pintype "power_in"))
      (node (ref "U1") (pin "2") (pinfunction "GND_2") (pintype "power_in"))
      (node (ref "U1") (pin "25") (pinfunction "GND_25") (pintype "power_in"))
      (node (ref "U1") (pin "26") (pinfunction "GND_26") (pintype "power_in"))
      (node (ref "U1") (pin "27") (pinfunction "IOB_n_27") (pintype "passive"))
      (node (ref "U1") (pin "31") (pinfunction "IOG_n_31") (pintype "passive"))
      (node (ref "U1") (pin "33") (pinfunction "IOR_n_33") (pintype "passive"))
      (node (ref "U1") (pin "39") (pinfunction "GND_39") (pintype "power_in"))
      (node (ref "U1") (pin "40") (pinfunction "GND_40") (pintype "power_in"))
      (node (ref "U1") (pin "49") (pinfunction "GND_49") (pintype "power_in"))
      (node (ref "U2") (pin "101") (pinfunction "VSS_101") (pintype "power_in"))
      (node (ref "U2") (pin "109") (pinfunction "VSS_109") (pintype "power_in"))
      (node (ref "U2") (pin "118") (pinfunction "VSS_118") (pintype "power_in"))
      (node (ref "U2") (pin "125") (pinfunction "VSS_125") (pintype "power_in"))
      (node (ref "U2") (pin "13") (pinfunction "VSS_13") (pintype "power_in"))
      (node (ref "U2") (pin "17") (pinfunction "VSS_17") (pintype "power_in"))
      (node (ref "U2") (pin "19") (pinfunction "VSSPLL_19") (pintype "power_in"))
      (node (ref "U2") (pin "2") (pinfunction "VSS_2") (pintype "power_in"))
      (node (ref "U2") (pin "20") (pinfunction "VSS_20") (pintype "power_in"))
      (node (ref "U2") (pin "22") (pinfunction "XTAL_IN_22") (pintype "passive"))
      (node (ref "U2") (pin "23") (pinfunction "VSS_23") (pintype "power_in"))
      (node (ref "U2") (pin "26") (pinfunction "VSS_26") (pintype "power_in"))
      (node (ref "U2") (pin "3") (pinfunction "VSS_3") (pintype "power_in"))
      (node (ref "U2") (pin "33") (pinfunction "VSS_33") (pintype "power_in"))
      (node (ref "U2") (pin "41") (pinfunction "VSS_41") (pintype "power_in"))
      (node (ref "U2") (pin "47") (pinfunction "VSS_47") (pintype "power_in"))
      (node (ref "U2") (pin "5") (pinfunction "VSS_5") (pintype "power_in"))
      (node (ref "U2") (pin "55") (pinfunction "VSS_55") (pintype "power_in"))
      (node (ref "U2") (pin "57") (pinfunction "VSS_57") (pintype "power_in"))
      (node (ref "U2") (pin "65") (pinfunction "VSS_65") (pintype "power_in"))
      (node (ref "U2") (pin "74") (pinfunction "VSS_74") (pintype "power_in"))
      (node (ref "U2") (pin "83") (pinfunction "VSS_83") (pintype "power_in"))
      (node (ref "U2") (pin "94") (pinfunction "VSS_94") (pintype "power_in"))
      (node (ref "U2") (pin "96") (pinfunction "VSS_96") (pintype "power_in"))
      (node (ref "X1") (pin "2") (pinfunction "GND_2") (pintype "power_in"))
    )
    (net (code "77") (name "Net-(J1-MH1)") (class "Default")
      (node (ref "C5") (pin "2") (pinfunction "2_2") (pintype "passive"))
      (node (ref "J1") (pin "16") (pinfunction "MH1_16") (pintype "passive"))
      (node (ref "J1") (pin "17") (pinfunction "MH2_17") (pintype "passive"))
    )
    (net (code "78") (name "Net-(J1-Pad13)") (class "Default")
      (node (ref "J1") (pin "13") (pinfunction "13_13") (pintype "passive"))
      (node (ref "R2") (pin "1") (pinfunction "1_1") (pintype "passive"))
    )
    (net (code "79") (name "Net-(J1-Pad14)") (class "Default")
      (node (ref "J1") (pin "14") (pinfunction "14_14") (pintype "passive"))
      (node (ref "R3") (pin "1") (pinfunction "1_1") (pintype "passive"))
    )
    (net (code "80") (name "Net-(J3-MH1)") (class "Default")
      (node (ref "C9") (pin "2") (pinfunction "2_2") (pintype "passive"))
      (node (ref "J3") (pin "16") (pinfunction "MH1_16") (pintype "passive"))
      (node (ref "J3") (pin "17") (pinfunction "MH2_17") (pintype "passive"))
    )
    (net (code "81") (name "Net-(J3-Pad1)") (class "Default")
      (node (ref "J3") (pin "1") (pinfunction "1_1") (pintype "passive"))
      (node (ref "R9") (pin "1") (pinfunction "1_1") (pintype "passive"))
    )
    (net (code "82") (name "Net-(J3-Pad2)") (class "Default")
      (node (ref "J3") (pin "2") (pinfunction "2_2") (pintype "passive"))
      (node (ref "R10") (pin "1") (pinfunction "1_1") (pintype "passive"))
    )
    (net (code "83") (name "Net-(J3-Pad3)") (class "Default")
      (node (ref "J3") (pin "3") (pinfunction "3_3") (pintype "passive"))
      (node (ref "R11") (pin "1") (pinfunction "1_1") (pintype "passive"))
    )
    (net (code "84") (name "Net-(J3-Pad13)") (class "Default")
      (node (ref "J3") (pin "13") (pinfunction "13_13") (pintype "passive"))
      (node (ref "R12") (pin "1") (pinfunction "1_1") (pintype "passive"))
    )
    (net (code "85") (name "Net-(J3-Pad14)") (class "Default")
      (node (ref "J3") (pin "14") (pinfunction "14_14") (pintype "passive"))
      (node (ref "R13") (pin "1") (pinfunction "1_1") (pintype "passive"))
    )
    (net (code "86") (name "Net-(U1-COMP)") (class "Default")
      (node (ref "C6") (pin "1") (pinfunction "1_1") (pintype "passive"))
      (node (ref "U1") (pin "35") (pinfunction "COMP_35") (pintype "passive"))
    )
    (net (code "87") (name "Net-(U1-PSAVE_n)") (class "Default")
      (node (ref "R7") (pin "2") (pinfunction "2_2") (pintype "passive"))
      (node (ref "U1") (pin "38") (pinfunction "PSAVE_n_38") (pintype "passive"))
    )
    (net (code "88") (name "Net-(U1-RSET)") (class "Default")
      (node (ref "R8") (pin "2") (pinfunction "2_2") (pintype "passive"))
      (node (ref "U1") (pin "37") (pinfunction "RSET_37") (pintype "passive"))
    )
    (net (code "89") (name "Net-(U1-VREF)") (class "Default")
      (node (ref "C4") (pin "1") (pinfunction "1_1") (pintype "passive"))
      (node (ref "D1") (pin "6") (pinfunction "VOUT_6") (pintype "passive"))
      (node (ref "D1") (pin "8") (pinfunction "VOUT_8") (pintype "passive"))
      (node (ref "R1") (pin "1") (pinfunction "1_1") (pintype "passive"))
      (node (ref "U1") (pin "36") (pinfunction "VREF_36") (pintype "power_in"))
    )
    (net (code "90") (name "unconnected-(J1-Pad4)") (class "Default")
      (node (ref "J1") (pin "4") (pinfunction "4_4") (pintype "passive+no_connect"))
    )
    (net (code "91") (name "unconnected-(J1-Pad9)") (class "Default")
      (node (ref "J1") (pin "9") (pinfunction "9_9") (pintype "passive+no_connect"))
    )
    (net (code "92") (name "unconnected-(J1-Pad11)") (class "Default")
      (node (ref "J1") (pin "11") (pinfunction "11_11") (pintype "passive+no_connect"))
    )
    (net (code "93") (name "unconnected-(J1-Pad12)") (class "Default")
      (node (ref "J1") (pin "12") (pinfunction "12_12") (pintype "passive+no_connect"))
    )
    (net (code "94") (name "unconnected-(J1-Pad15)") (class "Default")
      (node (ref "J1") (pin "15") (pinfunction "15_15") (pintype "passive+no_connect"))
    )
    (net (code "95") (name "unconnected-(J3-Pad4)") (class "Default")
      (node (ref "J3") (pin "4") (pinfunction "4_4") (pintype "passive+no_connect"))
    )
    (net (code "96") (name "unconnected-(J3-Pad9)") (class "Default")
      (node (ref "J3") (pin "9") (pinfunction "9_9") (pintype "passive+no_connect"))
    )
    (net (code "97") (name "unconnected-(J3-Pad11)") (class "Default")
      (node (ref "J3") (pin "11") (pinfunction "11_11") (pintype "passive+no_connect"))
    )
    (net (code "98") (name "unconnected-(J3-Pad12)") (class "Default")
      (node (ref "J3") (pin "12") (pinfunction "12_12") (pintype "passive+no_connect"))
    )
    (net (code "99") (name "unconnected-(J3-Pad15)") (class "Default")
      (node (ref "J3") (pin "15") (pinfunction "15_15") (pintype "passive+no_connect"))
    )
    (net (code "100") (name "unconnected-(U2A-GAMAS0-Pad52)") (class "Default")
      (node (ref "U2") (pin "52") (pinfunction "GAMAS0_52") (pintype "output+no_connect"))
    )
    (net (code "101") (name "unconnected-(U2A-GAMAS1-Pad53)") (class "Default")
      (node (ref "U2") (pin "53") (pinfunction "GAMAS1_53") (pintype "output+no_connect"))
    )
    (net (code "102") (name "unconnected-(U2A-GPIO3-Pad39)") (class "Default")
      (node (ref "U2") (pin "39") (pinfunction "GPIO3_39") (pintype "bidirectional+no_connect"))
    )
    (net (code "103") (name "unconnected-(U2A-LDEN-Pad49)") (class "Default")
      (node (ref "U2") (pin "49") (pinfunction "LDEN_49") (pintype "output+no_connect"))
    )
    (net (code "104") (name "unconnected-(U2A-PWM-Pad51)") (class "Default")
      (node (ref "U2") (pin "51") (pinfunction "PWM_51") (pintype "output+no_connect"))
    )
    (net (code "105") (name "unconnected-(U2A-XTAL_OUT-Pad24)") (class "Default")
      (node (ref "U2") (pin "24") (pinfunction "XTAL_OUT_24") (pintype "passive+no_connect"))
    )
    (net (code "106") (name "unconnected-(X1-NC-Pad1)") (class "Default")
      (node (ref "X1") (pin "1") (pinfunction "NC_1") (pintype "passive+no_connect"))
    )
  )
)
